# Shield_FT.net
KiCad netlist of a schematic drawn in EAGLE
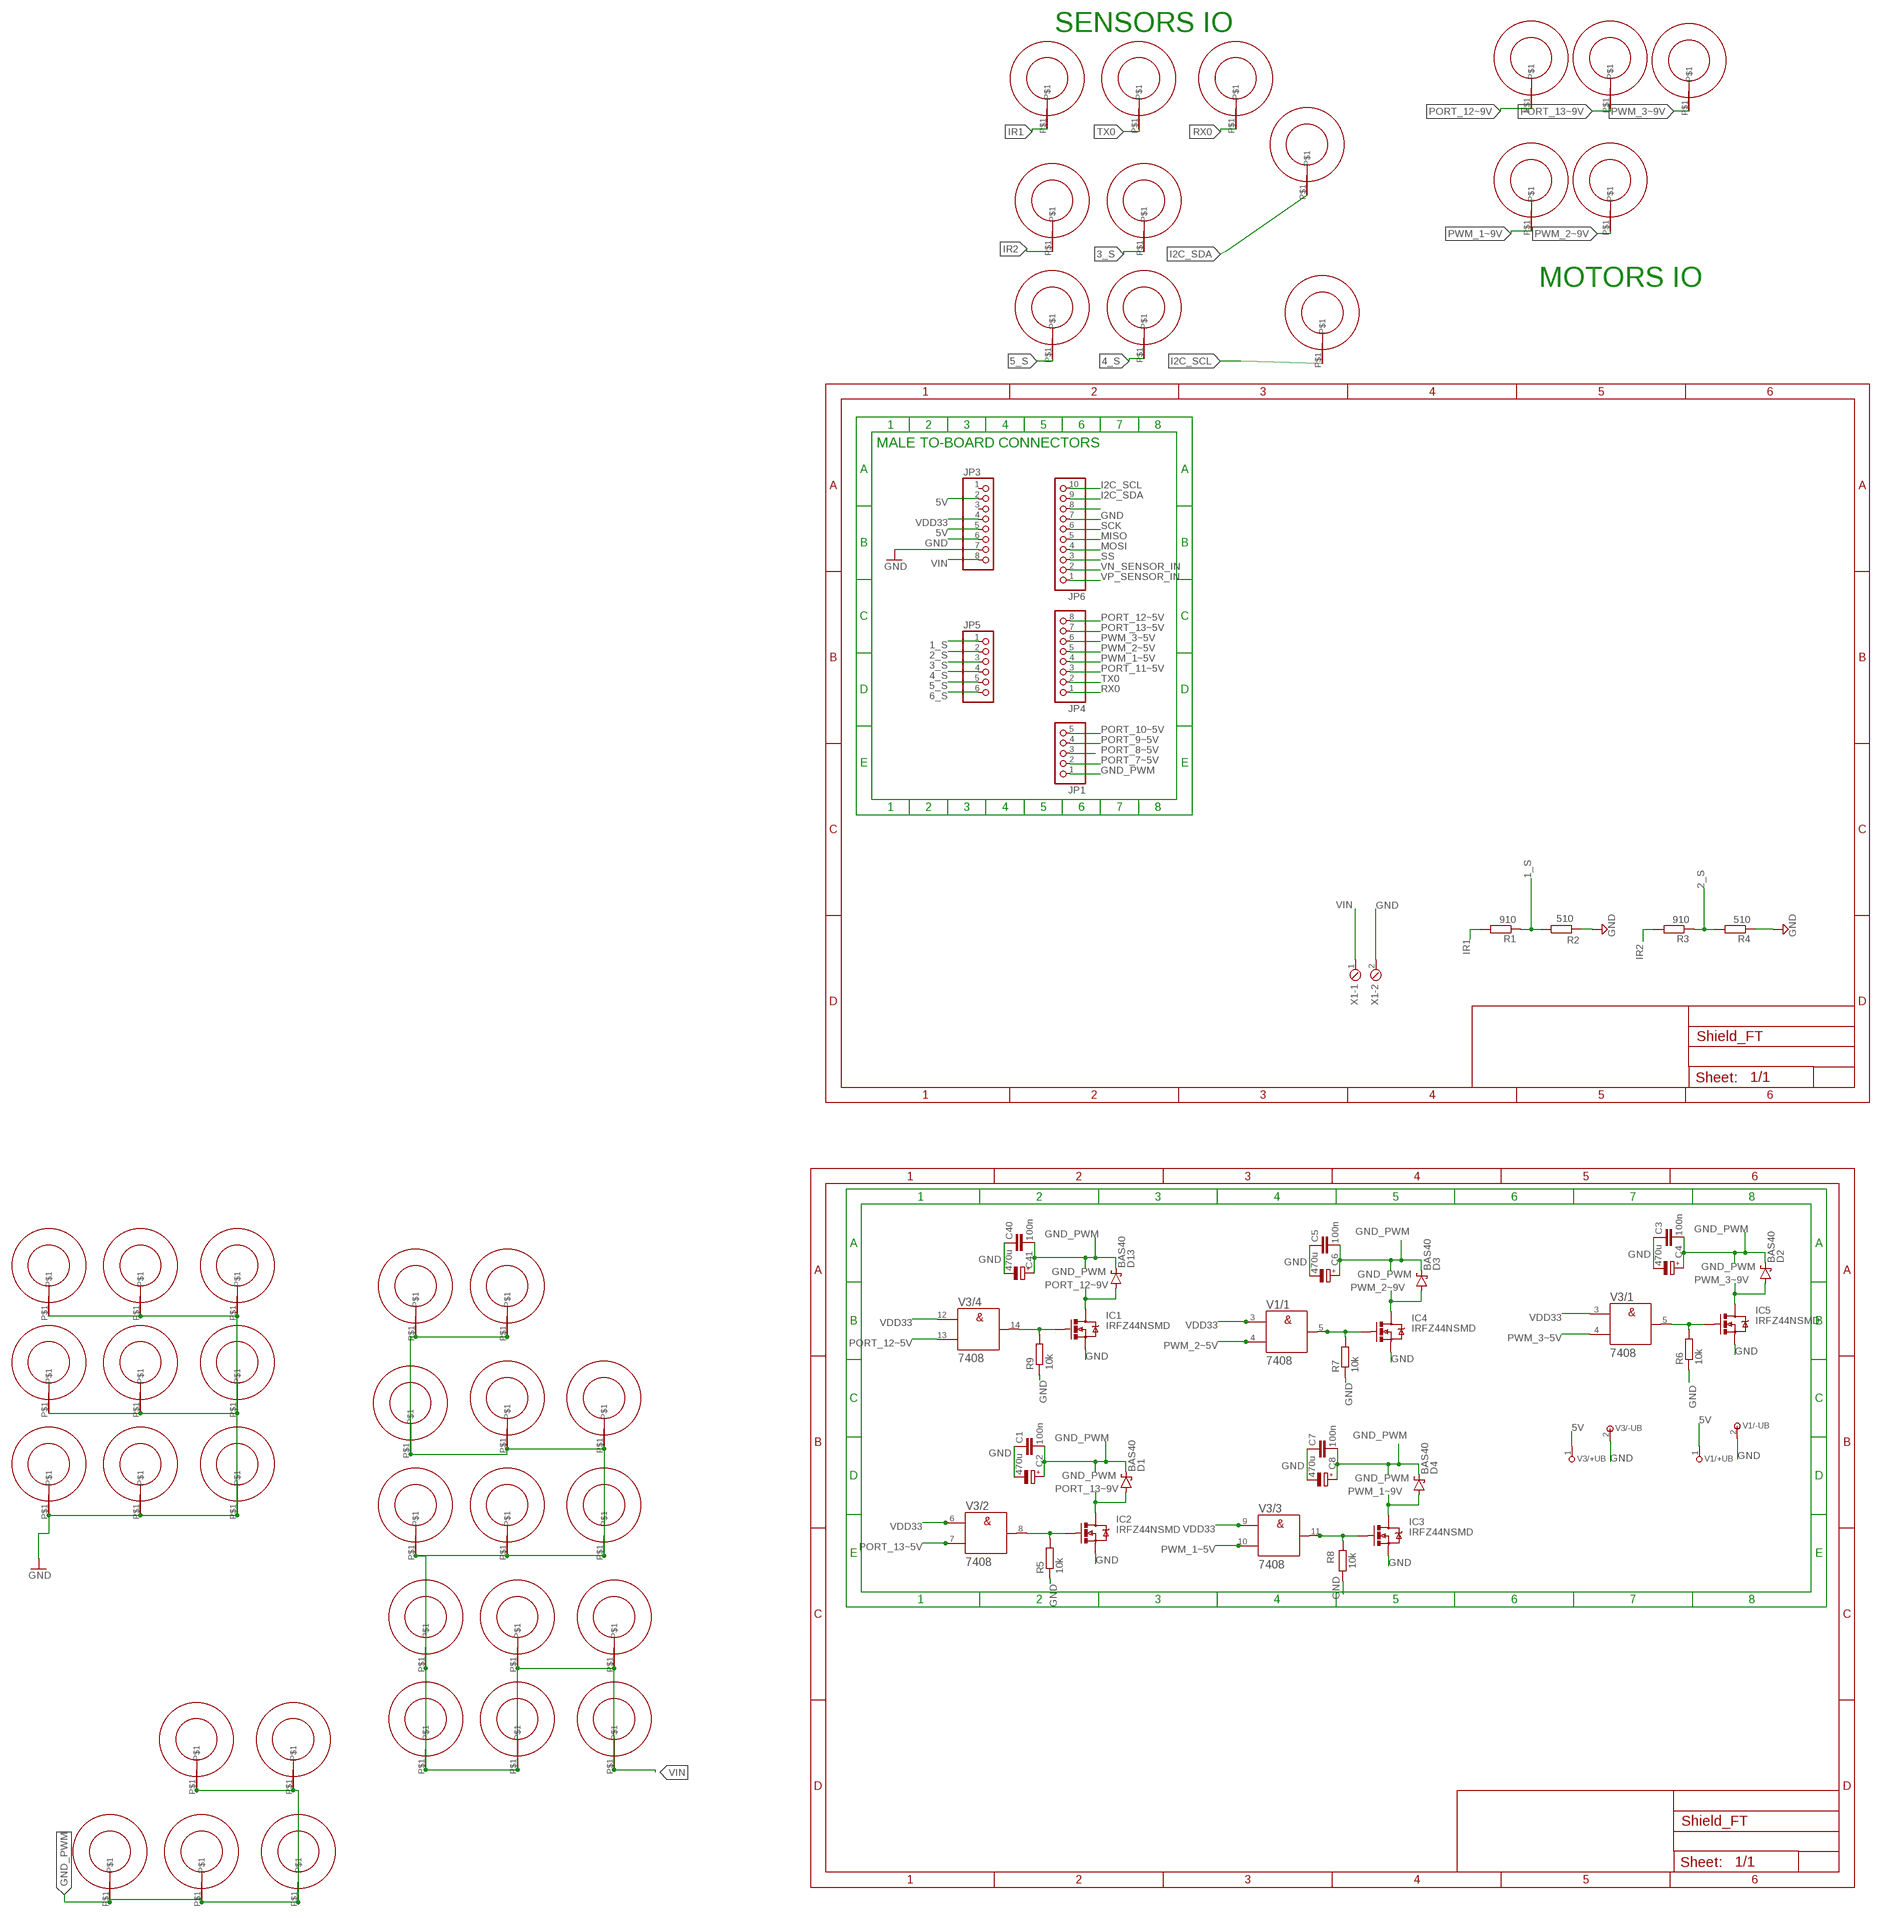
[diagram p0: schematic, sheet 1]

(export (version "E")
  (design (tool "Eeschema 10.0.6"))
  (components
    (comp (ref "C1")
      (value "100n")
      (footprint "eagle-import:C0402")
      (libsource (lib "eagle-import") (part "C-EUC0402"))
    )
    (comp (ref "C2")
      (value "470u")
      (footprint "eagle-import:PANASONIC_B_FT")
      (libsource (lib "eagle-import") (part "CPOL-EU"))
    )
    (comp (ref "C3")
      (value "100n")
      (footprint "eagle-import:C0402")
      (libsource (lib "eagle-import") (part "C-EUC0402"))
    )
    (comp (ref "C4")
      (value "470u")
      (footprint "eagle-import:PANASONIC_B_FT")
      (libsource (lib "eagle-import") (part "CPOL-EU"))
    )
    (comp (ref "C5")
      (value "100n")
      (footprint "eagle-import:C0402")
      (libsource (lib "eagle-import") (part "C-EUC0402"))
    )
    (comp (ref "C6")
      (value "470u")
      (footprint "eagle-import:PANASONIC_B_FT")
      (libsource (lib "eagle-import") (part "CPOL-EU"))
    )
    (comp (ref "C7")
      (value "100n")
      (footprint "eagle-import:C0402")
      (libsource (lib "eagle-import") (part "C-EUC0402"))
    )
    (comp (ref "C8")
      (value "470u")
      (footprint "eagle-import:PANASONIC_B_FT")
      (libsource (lib "eagle-import") (part "CPOL-EU"))
    )
    (comp (ref "C40")
      (value "100n")
      (footprint "eagle-import:C0402")
      (libsource (lib "eagle-import") (part "C-EUC0402"))
    )
    (comp (ref "C41")
      (value "470u")
      (footprint "eagle-import:PANASONIC_B_FT")
      (libsource (lib "eagle-import") (part "CPOL-EU"))
    )
    (comp (ref "D1")
      (value "BAS40")
      (footprint "eagle-import:SOT23")
      (libsource (lib "eagle-import") (part "BAS40"))
    )
    (comp (ref "D2")
      (value "BAS40")
      (footprint "eagle-import:SOT23")
      (libsource (lib "eagle-import") (part "BAS40"))
    )
    (comp (ref "D3")
      (value "BAS40")
      (footprint "eagle-import:SOT23")
      (libsource (lib "eagle-import") (part "BAS40"))
    )
    (comp (ref "D4")
      (value "BAS40")
      (footprint "eagle-import:SOT23")
      (libsource (lib "eagle-import") (part "BAS40"))
    )
    (comp (ref "D13")
      (value "BAS40")
      (footprint "eagle-import:SOT23")
      (libsource (lib "eagle-import") (part "BAS40"))
    )
    (comp (ref "IC1")
      (value "IRFZ44NSMD")
      (footprint "eagle-import:SMD")
      (libsource (lib "eagle-import") (part "IRFZ44NSMD"))
    )
    (comp (ref "IC2")
      (value "IRFZ44NSMD")
      (footprint "eagle-import:SMD")
      (libsource (lib "eagle-import") (part "IRFZ44NSMD"))
    )
    (comp (ref "IC3")
      (value "IRFZ44NSMD")
      (footprint "eagle-import:SMD")
      (libsource (lib "eagle-import") (part "IRFZ44NSMD"))
    )
    (comp (ref "IC4")
      (value "IRFZ44NSMD")
      (footprint "eagle-import:SMD")
      (libsource (lib "eagle-import") (part "IRFZ44NSMD"))
    )
    (comp (ref "IC5")
      (value "IRFZ44NSMD")
      (footprint "eagle-import:SMD")
      (libsource (lib "eagle-import") (part "IRFZ44NSMD"))
    )
    (comp (ref "JP1")
      (value "PINHD-1X5_2.54-SMD")
      (footprint "eagle-import:1X05SMD")
      (libsource (lib "eagle-import") (part "PINHD-1X5_2.54-SMD"))
    )
    (comp (ref "JP3")
      (value "PINHD-1X8_2.54-SMD")
      (footprint "eagle-import:1X08SMD")
      (libsource (lib "eagle-import") (part "PINHD-1X8_2.54-SMD"))
    )
    (comp (ref "JP4")
      (value "PINHD-1X8_2.54-SMD")
      (footprint "eagle-import:1X08SMD")
      (libsource (lib "eagle-import") (part "PINHD-1X8_2.54-SMD"))
    )
    (comp (ref "JP5")
      (value "PINHD-1X6_2.54-SMD")
      (footprint "eagle-import:1X06SMD")
      (libsource (lib "eagle-import") (part "PINHD-1X6_2.54-SMD"))
    )
    (comp (ref "JP6")
      (value "PINHD-1X10_2.54-SMD")
      (footprint "eagle-import:1X10SMD")
      (libsource (lib "eagle-import") (part "PINHD-1X10_2.54-SMD"))
    )
    (comp (ref "R1")
      (value "910")
      (footprint "eagle-import:M0805")
      (libsource (lib "eagle-import") (part "R-EU_M0805"))
    )
    (comp (ref "R2")
      (value "510")
      (footprint "eagle-import:M0805")
      (libsource (lib "eagle-import") (part "R-EU_M0805"))
    )
    (comp (ref "R3")
      (value "910")
      (footprint "eagle-import:M0805")
      (libsource (lib "eagle-import") (part "R-EU_M0805"))
    )
    (comp (ref "R4")
      (value "510")
      (footprint "eagle-import:M0805")
      (libsource (lib "eagle-import") (part "R-EU_M0805"))
    )
    (comp (ref "R5")
      (value "10k")
      (footprint "eagle-import:M0805")
      (libsource (lib "eagle-import") (part "R-EU_M0805"))
    )
    (comp (ref "R6")
      (value "10k")
      (footprint "eagle-import:M0805")
      (libsource (lib "eagle-import") (part "R-EU_M0805"))
    )
    (comp (ref "R7")
      (value "10k")
      (footprint "eagle-import:M0805")
      (libsource (lib "eagle-import") (part "R-EU_M0805"))
    )
    (comp (ref "R8")
      (value "10k")
      (footprint "eagle-import:M0805")
      (libsource (lib "eagle-import") (part "R-EU_M0805"))
    )
    (comp (ref "R9")
      (value "10k")
      (footprint "eagle-import:M0805")
      (libsource (lib "eagle-import") (part "R-EU_M0805"))
    )
    (comp (ref "U$1")
      (value "SOCKET")
      (footprint "eagle-import:SOCKET")
      (libsource (lib "eagle-import") (part "SOCKET"))
    )
    (comp (ref "U$2")
      (value "SOCKET")
      (footprint "eagle-import:SOCKET")
      (libsource (lib "eagle-import") (part "SOCKET"))
    )
    (comp (ref "U$3")
      (value "SOCKET")
      (footprint "eagle-import:SOCKET")
      (libsource (lib "eagle-import") (part "SOCKET"))
    )
    (comp (ref "U$7")
      (value "SOCKET")
      (footprint "eagle-import:SOCKET")
      (libsource (lib "eagle-import") (part "SOCKET"))
    )
    (comp (ref "U$8")
      (value "SOCKET")
      (footprint "eagle-import:SOCKET")
      (libsource (lib "eagle-import") (part "SOCKET"))
    )
    (comp (ref "U$11")
      (value "SOCKET")
      (footprint "eagle-import:SOCKET")
      (libsource (lib "eagle-import") (part "SOCKET"))
    )
    (comp (ref "U$12")
      (value "SOCKET")
      (footprint "eagle-import:SOCKET")
      (libsource (lib "eagle-import") (part "SOCKET"))
    )
    (comp (ref "U$13")
      (value "SOCKET")
      (footprint "eagle-import:SOCKET")
      (libsource (lib "eagle-import") (part "SOCKET"))
    )
    (comp (ref "U$14")
      (value "SOCKET")
      (footprint "eagle-import:SOCKET")
      (libsource (lib "eagle-import") (part "SOCKET"))
    )
    (comp (ref "U$43")
      (value "SOCKET")
      (footprint "eagle-import:SOCKET")
      (libsource (lib "eagle-import") (part "SOCKET"))
    )
    (comp (ref "U$44")
      (value "SOCKET")
      (footprint "eagle-import:SOCKET")
      (libsource (lib "eagle-import") (part "SOCKET"))
    )
    (comp (ref "U$45")
      (value "SOCKET")
      (footprint "eagle-import:SOCKET")
      (libsource (lib "eagle-import") (part "SOCKET"))
    )
    (comp (ref "U$46")
      (value "SOCKET")
      (footprint "eagle-import:SOCKET")
      (libsource (lib "eagle-import") (part "SOCKET"))
    )
    (comp (ref "U$47")
      (value "SOCKET")
      (footprint "eagle-import:SOCKET")
      (libsource (lib "eagle-import") (part "SOCKET"))
    )
    (comp (ref "U$48")
      (value "SOCKET")
      (footprint "eagle-import:SOCKET")
      (libsource (lib "eagle-import") (part "SOCKET"))
    )
    (comp (ref "U$49")
      (value "SOCKET")
      (footprint "eagle-import:SOCKET")
      (libsource (lib "eagle-import") (part "SOCKET"))
    )
    (comp (ref "U$50")
      (value "SOCKET")
      (footprint "eagle-import:SOCKET")
      (libsource (lib "eagle-import") (part "SOCKET"))
    )
    (comp (ref "U$51")
      (value "SOCKET")
      (footprint "eagle-import:SOCKET")
      (libsource (lib "eagle-import") (part "SOCKET"))
    )
    (comp (ref "U$52")
      (value "SOCKET")
      (footprint "eagle-import:SOCKET")
      (libsource (lib "eagle-import") (part "SOCKET"))
    )
    (comp (ref "U$53")
      (value "SOCKET")
      (footprint "eagle-import:SOCKET")
      (libsource (lib "eagle-import") (part "SOCKET"))
    )
    (comp (ref "U$54")
      (value "SOCKET")
      (footprint "eagle-import:SOCKET")
      (libsource (lib "eagle-import") (part "SOCKET"))
    )
    (comp (ref "U$55")
      (value "SOCKET")
      (footprint "eagle-import:SOCKET")
      (libsource (lib "eagle-import") (part "SOCKET"))
    )
    (comp (ref "U$56")
      (value "SOCKET")
      (footprint "eagle-import:SOCKET")
      (libsource (lib "eagle-import") (part "SOCKET"))
    )
    (comp (ref "U$57")
      (value "SOCKET")
      (footprint "eagle-import:SOCKET")
      (libsource (lib "eagle-import") (part "SOCKET"))
    )
    (comp (ref "U$58")
      (value "SOCKET")
      (footprint "eagle-import:SOCKET")
      (libsource (lib "eagle-import") (part "SOCKET"))
    )
    (comp (ref "U$59")
      (value "SOCKET")
      (footprint "eagle-import:SOCKET")
      (libsource (lib "eagle-import") (part "SOCKET"))
    )
    (comp (ref "U$60")
      (value "SOCKET")
      (footprint "eagle-import:SOCKET")
      (libsource (lib "eagle-import") (part "SOCKET"))
    )
    (comp (ref "U$61")
      (value "SOCKET")
      (footprint "eagle-import:SOCKET")
      (libsource (lib "eagle-import") (part "SOCKET"))
    )
    (comp (ref "U$62")
      (value "SOCKET")
      (footprint "eagle-import:SOCKET")
      (libsource (lib "eagle-import") (part "SOCKET"))
    )
    (comp (ref "U$63")
      (value "SOCKET")
      (footprint "eagle-import:SOCKET")
      (libsource (lib "eagle-import") (part "SOCKET"))
    )
    (comp (ref "U$64")
      (value "SOCKET")
      (footprint "eagle-import:SOCKET")
      (libsource (lib "eagle-import") (part "SOCKET"))
    )
    (comp (ref "U$65")
      (value "SOCKET")
      (footprint "eagle-import:SOCKET")
      (libsource (lib "eagle-import") (part "SOCKET"))
    )
    (comp (ref "U$66")
      (value "SOCKET")
      (footprint "eagle-import:SOCKET")
      (libsource (lib "eagle-import") (part "SOCKET"))
    )
    (comp (ref "U$68")
      (value "SOCKET")
      (footprint "eagle-import:SOCKET")
      (libsource (lib "eagle-import") (part "SOCKET"))
    )
    (comp (ref "U$69")
      (value "SOCKET")
      (footprint "eagle-import:SOCKET")
      (libsource (lib "eagle-import") (part "SOCKET"))
    )
    (comp (ref "U$70")
      (value "SOCKET")
      (footprint "eagle-import:SOCKET")
      (libsource (lib "eagle-import") (part "SOCKET"))
    )
    (comp (ref "U$71")
      (value "SOCKET")
      (footprint "eagle-import:SOCKET")
      (libsource (lib "eagle-import") (part "SOCKET"))
    )
    (comp (ref "U$73")
      (value "SOCKET")
      (footprint "eagle-import:SOCKET")
      (libsource (lib "eagle-import") (part "SOCKET"))
    )
    (comp (ref "U$74")
      (value "SOCKET")
      (footprint "eagle-import:SOCKET")
      (libsource (lib "eagle-import") (part "SOCKET"))
    )
    (comp (ref "U$75")
      (value "SOCKET")
      (footprint "eagle-import:SOCKET")
      (libsource (lib "eagle-import") (part "SOCKET"))
    )
    (comp (ref "U$77")
      (value "SOCKET")
      (footprint "eagle-import:SOCKET")
      (libsource (lib "eagle-import") (part "SOCKET"))
    )
    (comp (ref "U$78")
      (value "SOCKET")
      (footprint "eagle-import:SOCKET")
      (libsource (lib "eagle-import") (part "SOCKET"))
    )
    (comp (ref "V1")
      (value "7408")
      (footprint "eagle-import:DIL14_FT")
      (libsource (lib "eagle-import") (part "7408"))
    )
    (comp (ref "V3")
      (value "7408")
      (footprint "eagle-import:DIL14_FT")
      (libsource (lib "eagle-import") (part "7408"))
    )
    (comp (ref "X1")
      (value "MPT21.3")
      (footprint "eagle-import:2POL254_1.3")
      (libsource (lib "eagle-import") (part "MPT21.3"))
    )
  )
  (nets
    (net (code "1") (name "/1_S") (class "Default")
      (node (ref "JP5") (pin "1") (pinfunction "1_1") (pintype "passive"))
      (node (ref "R1") (pin "1") (pinfunction "1_1") (pintype "passive"))
      (node (ref "R2") (pin "1") (pinfunction "1_1") (pintype "passive"))
    )
    (net (code "2") (name "/2_S") (class "Default")
      (node (ref "JP5") (pin "2") (pinfunction "2_2") (pintype "passive"))
      (node (ref "R3") (pin "1") (pinfunction "1_1") (pintype "passive"))
      (node (ref "R4") (pin "2") (pinfunction "2_2") (pintype "passive"))
    )
    (net (code "3") (name "/5V") (class "Default")
      (node (ref "JP3") (pin "2") (pinfunction "2_2") (pintype "passive"))
      (node (ref "JP3") (pin "5") (pinfunction "5_5") (pintype "passive"))
      (node (ref "V1") (pin "1") (pinfunction "+UB_1") (pintype "power_in"))
      (node (ref "V3") (pin "1") (pinfunction "+UB_1") (pintype "power_in"))
    )
    (net (code "4") (name "/6_S") (class "Default")
      (node (ref "JP5") (pin "6") (pinfunction "6_6") (pintype "passive"))
    )
    (net (code "5") (name "/MISO") (class "Default")
      (node (ref "JP6") (pin "5") (pinfunction "5_5") (pintype "passive"))
    )
    (net (code "6") (name "/MOSI") (class "Default")
      (node (ref "JP6") (pin "4") (pinfunction "4_4") (pintype "passive"))
    )
    (net (code "7") (name "/PORT_7~{5V}") (class "Default")
      (node (ref "JP1") (pin "2") (pinfunction "2_2") (pintype "passive"))
    )
    (net (code "8") (name "/PORT_8~{5V}") (class "Default")
      (node (ref "JP1") (pin "3") (pinfunction "3_3") (pintype "passive"))
    )
    (net (code "9") (name "/PORT_9~{5V}") (class "Default")
      (node (ref "JP1") (pin "4") (pinfunction "4_4") (pintype "passive"))
    )
    (net (code "10") (name "/PORT_10~{5V}") (class "Default")
      (node (ref "JP1") (pin "5") (pinfunction "5_5") (pintype "passive"))
    )
    (net (code "11") (name "/PORT_11~{5V}") (class "Default")
      (node (ref "JP4") (pin "3") (pinfunction "3_3") (pintype "passive"))
    )
    (net (code "12") (name "/PORT_12~{5V}") (class "Default")
      (node (ref "JP4") (pin "8") (pinfunction "8_8") (pintype "passive"))
      (node (ref "V3") (pin "13") (pinfunction "B_13") (pintype "input"))
    )
    (net (code "13") (name "/PORT_12~{9V}") (class "Default")
      (node (ref "D13") (pin "1") (pinfunction "A_1") (pintype "passive"))
      (node (ref "IC1") (pin "2") (pinfunction "D_2") (pintype "passive"))
      (node (ref "U$11") (pin "P$1") (pinfunction "P$1_P$1") (pintype "bidirectional"))
    )
    (net (code "14") (name "/PORT_13~{5V}") (class "Default")
      (node (ref "JP4") (pin "7") (pinfunction "7_7") (pintype "passive"))
      (node (ref "V3") (pin "7") (pinfunction "B_7") (pintype "input"))
    )
    (net (code "15") (name "/PORT_13~{9V}") (class "Default")
      (node (ref "D1") (pin "1") (pinfunction "A_1") (pintype "passive"))
      (node (ref "IC2") (pin "2") (pinfunction "D_2") (pintype "passive"))
      (node (ref "U$14") (pin "P$1") (pinfunction "P$1_P$1") (pintype "bidirectional"))
    )
    (net (code "16") (name "/PWM_1~{5V}") (class "Default")
      (node (ref "JP4") (pin "4") (pinfunction "4_4") (pintype "passive"))
      (node (ref "V3") (pin "10") (pinfunction "B_10") (pintype "input"))
    )
    (net (code "17") (name "/PWM_1~{9V}") (class "Default")
      (node (ref "D4") (pin "1") (pinfunction "A_1") (pintype "passive"))
      (node (ref "IC3") (pin "2") (pinfunction "D_2") (pintype "passive"))
      (node (ref "U$2") (pin "P$1") (pinfunction "P$1_P$1") (pintype "bidirectional"))
    )
    (net (code "18") (name "/PWM_2~{5V}") (class "Default")
      (node (ref "JP4") (pin "5") (pinfunction "5_5") (pintype "passive"))
      (node (ref "V1") (pin "4") (pinfunction "B_4") (pintype "input"))
    )
    (net (code "19") (name "/PWM_2~{9V}") (class "Default")
      (node (ref "D3") (pin "1") (pinfunction "A_1") (pintype "passive"))
      (node (ref "IC4") (pin "2") (pinfunction "D_2") (pintype "passive"))
      (node (ref "U$3") (pin "P$1") (pinfunction "P$1_P$1") (pintype "bidirectional"))
    )
    (net (code "20") (name "/PWM_3~{5V}") (class "Default")
      (node (ref "JP4") (pin "6") (pinfunction "6_6") (pintype "passive"))
      (node (ref "V3") (pin "4") (pinfunction "B_4") (pintype "input"))
    )
    (net (code "21") (name "/PWM_3~{9V}") (class "Default")
      (node (ref "D2") (pin "1") (pinfunction "A_1") (pintype "passive"))
      (node (ref "IC5") (pin "2") (pinfunction "D_2") (pintype "passive"))
      (node (ref "U$12") (pin "P$1") (pinfunction "P$1_P$1") (pintype "bidirectional"))
    )
    (net (code "22") (name "/SCK") (class "Default")
      (node (ref "JP6") (pin "6") (pinfunction "6_6") (pintype "passive"))
    )
    (net (code "23") (name "/SS") (class "Default")
      (node (ref "JP6") (pin "3") (pinfunction "3_3") (pintype "passive"))
    )
    (net (code "24") (name "/VDD33") (class "Default")
      (node (ref "JP3") (pin "4") (pinfunction "4_4") (pintype "passive"))
      (node (ref "V1") (pin "3") (pinfunction "A_3") (pintype "input"))
      (node (ref "V3") (pin "12") (pinfunction "A_12") (pintype "input"))
      (node (ref "V3") (pin "3") (pinfunction "A_3") (pintype "input"))
      (node (ref "V3") (pin "6") (pinfunction "A_6") (pintype "input"))
      (node (ref "V3") (pin "9") (pinfunction "A_9") (pintype "input"))
    )
    (net (code "25") (name "/VN_SENSOR_IN") (class "Default")
      (node (ref "JP6") (pin "2") (pinfunction "2_2") (pintype "passive"))
    )
    (net (code "26") (name "/VP_SENSOR_IN") (class "Default")
      (node (ref "JP6") (pin "1") (pinfunction "1_1") (pintype "passive"))
    )
    (net (code "27") (name "3_S") (class "Default")
      (node (ref "JP5") (pin "3") (pinfunction "3_3") (pintype "passive"))
      (node (ref "U$8") (pin "P$1") (pinfunction "P$1_P$1") (pintype "bidirectional"))
    )
    (net (code "28") (name "4_S") (class "Default")
      (node (ref "JP5") (pin "4") (pinfunction "4_4") (pintype "passive"))
      (node (ref "U$44") (pin "P$1") (pinfunction "P$1_P$1") (pintype "bidirectional"))
    )
    (net (code "29") (name "5_S") (class "Default")
      (node (ref "JP5") (pin "5") (pinfunction "5_5") (pintype "passive"))
      (node (ref "U$43") (pin "P$1") (pinfunction "P$1_P$1") (pintype "bidirectional"))
    )
    (net (code "30") (name "GND") (class "Default")
      (node (ref "C1") (pin "1") (pinfunction "1_1") (pintype "passive"))
      (node (ref "C2") (pin "-") (pinfunction "-_-") (pintype "passive"))
      (node (ref "C3") (pin "1") (pinfunction "1_1") (pintype "passive"))
      (node (ref "C4") (pin "-") (pinfunction "-_-") (pintype "passive"))
      (node (ref "C40") (pin "1") (pinfunction "1_1") (pintype "passive"))
      (node (ref "C41") (pin "-") (pinfunction "-_-") (pintype "passive"))
      (node (ref "C5") (pin "1") (pinfunction "1_1") (pintype "passive"))
      (node (ref "C6") (pin "-") (pinfunction "-_-") (pintype "passive"))
      (node (ref "C7") (pin "1") (pinfunction "1_1") (pintype "passive"))
      (node (ref "C8") (pin "-") (pinfunction "-_-") (pintype "passive"))
      (node (ref "IC1") (pin "3") (pinfunction "S_3") (pintype "passive"))
      (node (ref "IC2") (pin "3") (pinfunction "S_3") (pintype "passive"))
      (node (ref "IC3") (pin "3") (pinfunction "S_3") (pintype "passive"))
      (node (ref "IC4") (pin "3") (pinfunction "S_3") (pintype "passive"))
      (node (ref "IC5") (pin "3") (pinfunction "S_3") (pintype "passive"))
      (node (ref "JP3") (pin "6") (pinfunction "6_6") (pintype "passive"))
      (node (ref "JP3") (pin "7") (pinfunction "7_7") (pintype "passive"))
      (node (ref "JP6") (pin "7") (pinfunction "7_7") (pintype "passive"))
      (node (ref "R2") (pin "2") (pinfunction "2_2") (pintype "passive"))
      (node (ref "R4") (pin "1") (pinfunction "1_1") (pintype "passive"))
      (node (ref "R5") (pin "1") (pinfunction "1_1") (pintype "passive"))
      (node (ref "R6") (pin "1") (pinfunction "1_1") (pintype "passive"))
      (node (ref "R7") (pin "1") (pinfunction "1_1") (pintype "passive"))
      (node (ref "R8") (pin "1") (pinfunction "1_1") (pintype "passive"))
      (node (ref "R9") (pin "1") (pinfunction "1_1") (pintype "passive"))
      (node (ref "U$49") (pin "P$1") (pinfunction "P$1_P$1") (pintype "bidirectional"))
      (node (ref "U$50") (pin "P$1") (pinfunction "P$1_P$1") (pintype "bidirectional"))
      (node (ref "U$51") (pin "P$1") (pinfunction "P$1_P$1") (pintype "bidirectional"))
      (node (ref "U$52") (pin "P$1") (pinfunction "P$1_P$1") (pintype "bidirectional"))
      (node (ref "U$53") (pin "P$1") (pinfunction "P$1_P$1") (pintype "bidirectional"))
      (node (ref "U$54") (pin "P$1") (pinfunction "P$1_P$1") (pintype "bidirectional"))
      (node (ref "U$55") (pin "P$1") (pinfunction "P$1_P$1") (pintype "bidirectional"))
      (node (ref "U$56") (pin "P$1") (pinfunction "P$1_P$1") (pintype "bidirectional"))
      (node (ref "U$57") (pin "P$1") (pinfunction "P$1_P$1") (pintype "bidirectional"))
      (node (ref "V1") (pin "2") (pinfunction "-UB_2") (pintype "power_in"))
      (node (ref "V3") (pin "2") (pinfunction "-UB_2") (pintype "power_in"))
      (node (ref "X1") (pin "2") (pinfunction "1_2") (pintype "passive"))
    )
    (net (code "31") (name "GND_PWM") (class "Default")
      (node (ref "C1") (pin "2") (pinfunction "2_2") (pintype "passive"))
      (node (ref "C2") (pin "+") (pinfunction "+_+") (pintype "passive"))
      (node (ref "C3") (pin "2") (pinfunction "2_2") (pintype "passive"))
      (node (ref "C4") (pin "+") (pinfunction "+_+") (pintype "passive"))
      (node (ref "C40") (pin "2") (pinfunction "2_2") (pintype "passive"))
      (node (ref "C41") (pin "+") (pinfunction "+_+") (pintype "passive"))
      (node (ref "C5") (pin "2") (pinfunction "2_2") (pintype "passive"))
      (node (ref "C6") (pin "+") (pinfunction "+_+") (pintype "passive"))
      (node (ref "C7") (pin "2") (pinfunction "2_2") (pintype "passive"))
      (node (ref "C8") (pin "+") (pinfunction "+_+") (pintype "passive"))
      (node (ref "D1") (pin "3") (pinfunction "C_3") (pintype "passive"))
      (node (ref "D13") (pin "3") (pinfunction "C_3") (pintype "passive"))
      (node (ref "D2") (pin "3") (pinfunction "C_3") (pintype "passive"))
      (node (ref "D3") (pin "3") (pinfunction "C_3") (pintype "passive"))
      (node (ref "D4") (pin "3") (pinfunction "C_3") (pintype "passive"))
      (node (ref "JP1") (pin "1") (pinfunction "1_1") (pintype "passive"))
      (node (ref "U$73") (pin "P$1") (pinfunction "P$1_P$1") (pintype "bidirectional"))
      (node (ref "U$74") (pin "P$1") (pinfunction "P$1_P$1") (pintype "bidirectional"))
      (node (ref "U$75") (pin "P$1") (pinfunction "P$1_P$1") (pintype "bidirectional"))
      (node (ref "U$77") (pin "P$1") (pinfunction "P$1_P$1") (pintype "bidirectional"))
      (node (ref "U$78") (pin "P$1") (pinfunction "P$1_P$1") (pintype "bidirectional"))
    )
    (net (code "32") (name "I2C_SCL") (class "Default")
      (node (ref "JP6") (pin "10") (pinfunction "10_10") (pintype "passive"))
      (node (ref "U$45") (pin "P$1") (pinfunction "P$1_P$1") (pintype "bidirectional"))
    )
    (net (code "33") (name "I2C_SDA") (class "Default")
      (node (ref "JP6") (pin "9") (pinfunction "9_9") (pintype "passive"))
      (node (ref "U$13") (pin "P$1") (pinfunction "P$1_P$1") (pintype "bidirectional"))
    )
    (net (code "34") (name "IR1") (class "Default")
      (node (ref "R1") (pin "2") (pinfunction "2_2") (pintype "passive"))
      (node (ref "U$46") (pin "P$1") (pinfunction "P$1_P$1") (pintype "bidirectional"))
    )
    (net (code "35") (name "IR2") (class "Default")
      (node (ref "R3") (pin "2") (pinfunction "2_2") (pintype "passive"))
      (node (ref "U$7") (pin "P$1") (pinfunction "P$1_P$1") (pintype "bidirectional"))
    )
    (net (code "36") (name "Net-(IC1-G)") (class "Default")
      (node (ref "IC1") (pin "1") (pinfunction "G_1") (pintype "passive"))
      (node (ref "R9") (pin "2") (pinfunction "2_2") (pintype "passive"))
      (node (ref "V3") (pin "14") (pinfunction "Y_14") (pintype "output"))
    )
    (net (code "37") (name "Net-(IC2-G)") (class "Default")
      (node (ref "IC2") (pin "1") (pinfunction "G_1") (pintype "passive"))
      (node (ref "R5") (pin "2") (pinfunction "2_2") (pintype "passive"))
      (node (ref "V3") (pin "8") (pinfunction "Y_8") (pintype "output"))
    )
    (net (code "38") (name "Net-(IC3-G)") (class "Default")
      (node (ref "IC3") (pin "1") (pinfunction "G_1") (pintype "passive"))
      (node (ref "R8") (pin "2") (pinfunction "2_2") (pintype "passive"))
      (node (ref "V3") (pin "11") (pinfunction "Y_11") (pintype "output"))
    )
    (net (code "39") (name "Net-(IC4-G)") (class "Default")
      (node (ref "IC4") (pin "1") (pinfunction "G_1") (pintype "passive"))
      (node (ref "R7") (pin "2") (pinfunction "2_2") (pintype "passive"))
      (node (ref "V1") (pin "5") (pinfunction "Y_5") (pintype "output"))
    )
    (net (code "40") (name "Net-(IC5-G)") (class "Default")
      (node (ref "IC5") (pin "1") (pinfunction "G_1") (pintype "passive"))
      (node (ref "R6") (pin "2") (pinfunction "2_2") (pintype "passive"))
      (node (ref "V3") (pin "5") (pinfunction "Y_5") (pintype "output"))
    )
    (net (code "41") (name "RX0") (class "Default")
      (node (ref "JP4") (pin "1") (pinfunction "1_1") (pintype "passive"))
      (node (ref "U$48") (pin "P$1") (pinfunction "P$1_P$1") (pintype "bidirectional"))
    )
    (net (code "42") (name "TX0") (class "Default")
      (node (ref "JP4") (pin "2") (pinfunction "2_2") (pintype "passive"))
      (node (ref "U$47") (pin "P$1") (pinfunction "P$1_P$1") (pintype "bidirectional"))
    )
    (net (code "43") (name "VIN") (class "Default")
      (node (ref "JP3") (pin "8") (pinfunction "8_8") (pintype "passive"))
      (node (ref "U$1") (pin "P$1") (pinfunction "P$1_P$1") (pintype "bidirectional"))
      (node (ref "U$58") (pin "P$1") (pinfunction "P$1_P$1") (pintype "bidirectional"))
      (node (ref "U$59") (pin "P$1") (pinfunction "P$1_P$1") (pintype "bidirectional"))
      (node (ref "U$60") (pin "P$1") (pinfunction "P$1_P$1") (pintype "bidirectional"))
      (node (ref "U$61") (pin "P$1") (pinfunction "P$1_P$1") (pintype "bidirectional"))
      (node (ref "U$62") (pin "P$1") (pinfunction "P$1_P$1") (pintype "bidirectional"))
      (node (ref "U$63") (pin "P$1") (pinfunction "P$1_P$1") (pintype "bidirectional"))
      (node (ref "U$64") (pin "P$1") (pinfunction "P$1_P$1") (pintype "bidirectional"))
      (node (ref "U$65") (pin "P$1") (pinfunction "P$1_P$1") (pintype "bidirectional"))
      (node (ref "U$66") (pin "P$1") (pinfunction "P$1_P$1") (pintype "bidirectional"))
      (node (ref "U$68") (pin "P$1") (pinfunction "P$1_P$1") (pintype "bidirectional"))
      (node (ref "U$69") (pin "P$1") (pinfunction "P$1_P$1") (pintype "bidirectional"))
      (node (ref "U$70") (pin "P$1") (pinfunction "P$1_P$1") (pintype "bidirectional"))
      (node (ref "U$71") (pin "P$1") (pinfunction "P$1_P$1") (pintype "bidirectional"))
      (node (ref "X1") (pin "1") (pinfunction "1_1") (pintype "passive"))
    )
    (net (code "44") (name "unconnected-(JP3-Pad1)") (class "Default")
      (node (ref "JP3") (pin "1") (pinfunction "1_1") (pintype "passive"))
    )
    (net (code "45") (name "unconnected-(JP3-Pad3)") (class "Default")
      (node (ref "JP3") (pin "3") (pinfunction "3_3") (pintype "passive"))
    )
    (net (code "46") (name "unconnected-(JP6-Pad8)") (class "Default")
      (node (ref "JP6") (pin "8") (pinfunction "8_8") (pintype "passive"))
    )
  )
)
